# analog_channel.net
KiCad netlist of a schematic drawn in Altium Designer
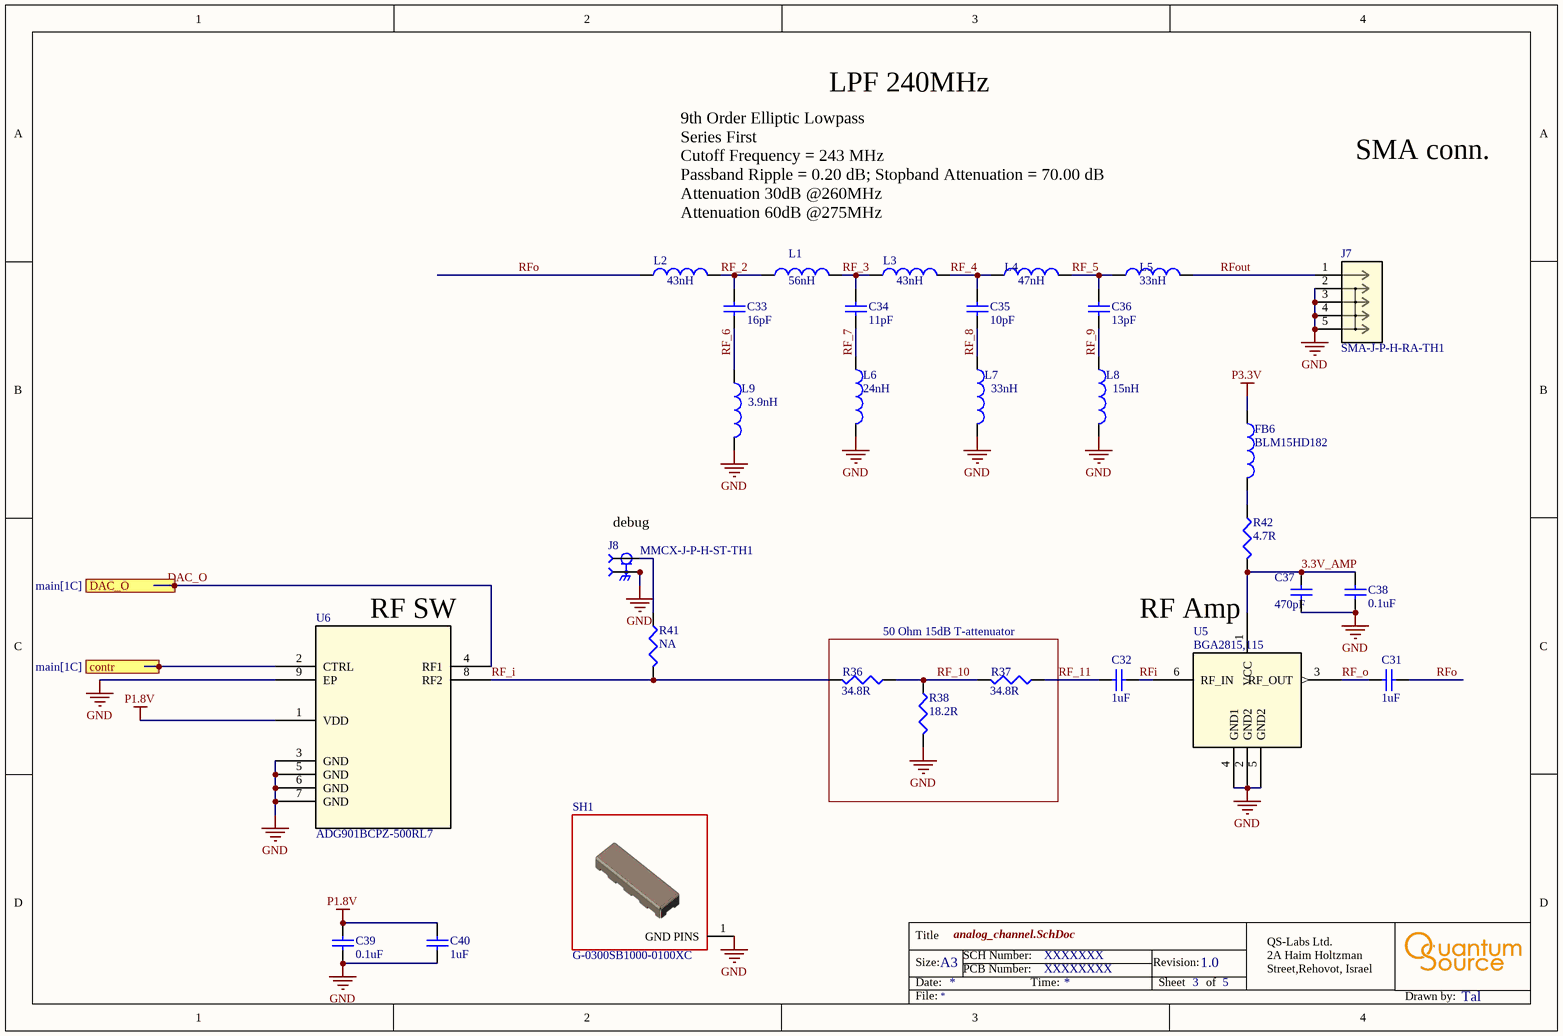
[diagram p0: analog_channel.SchDoc]

(export (version "E")
  (design (tool "Eeschema 10.0.6"))
  (components
    (comp (ref "C31")
      (value "1uF 25V")
      (footprint "C0402")
      (description "CAP CER 1uF 25V X5R 0402")
      (fields
        (field (name "MANUFACTURER PART NUMBER") "C1005C0G1H6R8D")
        (field (name "MANUFACTURER") "TDK Corporation")
        (field (name "CAPACITANCE") "1uF")
      )
      (libsource (lib "L_SCH_C") (part "CAP CER 6.8pF 50V NP0 0402"))
    )
    (comp (ref "C32")
      (value "1uF 25V")
      (footprint "C0402")
      (description "CAP CER 1uF 25V X5R 0402")
      (fields
        (field (name "MANUFACTURER PART NUMBER") "C1005C0G1H6R8D")
        (field (name "MANUFACTURER") "TDK Corporation")
        (field (name "CAPACITANCE") "1uF")
      )
      (libsource (lib "L_SCH_C") (part "CAP CER 6.8pF 50V NP0 0402"))
    )
    (comp (ref "C33")
      (value "16pF 50V")
      (footprint "C0402")
      (description "CAP CER 16PF 50V 5% NP0 0402")
      (fields
        (field (name "MANUFACTURER") "TDK Corporation")
        (field (name "MANUFACTURER PART NUMBER") "C1005C0G1H200J")
        (field (name "CAPACITANCE") "16pF")
      )
      (libsource (lib "L_SCH_C") (part "CAP CER 20pF 50V 5% NP0 0402"))
    )
    (comp (ref "C34")
      (value "11pF 50V")
      (footprint "C0402")
      (description "CAP CER 11PF 50V 5% NP0 0402")
      (fields
        (field (name "MANUFACTURER") "TDK Corporation")
        (field (name "MANUFACTURER PART NUMBER") "C1005C0G1H200J")
        (field (name "CAPACITANCE") "11pF")
      )
      (libsource (lib "L_SCH_C") (part "CAP CER 20pF 50V 5% NP0 0402"))
    )
    (comp (ref "C35")
      (value "10pF 50V")
      (footprint "C0402")
      (description "CAP CER 10PF 50V 5% NP0 0402")
      (fields
        (field (name "MANUFACTURER") "TDK Corporation")
        (field (name "MANUFACTURER PART NUMBER") "C1005C0G1H200J")
        (field (name "CAPACITANCE") "10pF")
      )
      (libsource (lib "L_SCH_C") (part "CAP CER 20pF 50V 5% NP0 0402"))
    )
    (comp (ref "C36")
      (value "13pF 50V")
      (footprint "C0402")
      (description "CAP CER 13PF 50V 5% NP0 0402")
      (fields
        (field (name "MANUFACTURER") "TDK Corporation")
        (field (name "MANUFACTURER PART NUMBER") "C1005C0G1H200J")
        (field (name "CAPACITANCE") "13pF")
      )
      (libsource (lib "L_SCH_C") (part "CAP CER 20pF 50V 5% NP0 0402"))
    )
    (comp (ref "C37")
      (value "470pF 25V")
      (footprint "C0402")
      (description "CAP CER 470pF 25V X5R 0402")
      (fields
        (field (name "MANUFACTURER PART NUMBER") "C1005C0G1H6R8D")
        (field (name "MANUFACTURER") "TDK Corporation")
        (field (name "CAPACITANCE") "470pF")
      )
      (libsource (lib "L_SCH_C") (part "CAP CER 6.8pF 50V NP0 0402"))
    )
    (comp (ref "C38")
      (value "0.1uF 50V")
      (footprint "C0402")
      (description "CAP CER 0.1uF 50V NP0 0402")
      (fields
        (field (name "MANUFACTURER PART NUMBER") "C1005C0G1H6R8D")
        (field (name "MANUFACTURER") "TDK Corporation")
        (field (name "CAPACITANCE") "0.1uF")
      )
      (libsource (lib "L_SCH_C") (part "CAP CER 6.8pF 50V NP0 0402"))
    )
    (comp (ref "C39")
      (value "0.1uF 50V")
      (footprint "C0402")
      (description "CAP CER 0.1uF 50V NP0 0402")
      (fields
        (field (name "MANUFACTURER PART NUMBER") "C1005C0G1H6R8D")
        (field (name "MANUFACTURER") "TDK Corporation")
        (field (name "CAPACITANCE") "0.1uF")
      )
      (libsource (lib "L_SCH_C") (part "CAP CER 6.8pF 50V NP0 0402"))
    )
    (comp (ref "C40")
      (value "1uF 25V")
      (footprint "C0402")
      (description "CAP CER 1uF 25V X5R 0402")
      (fields
        (field (name "MANUFACTURER PART NUMBER") "C1005C0G1H6R8D")
        (field (name "MANUFACTURER") "TDK Corporation")
        (field (name "CAPACITANCE") "1uF")
      )
      (libsource (lib "L_SCH_C") (part "CAP CER 6.8pF 50V NP0 0402"))
    )
    (comp (ref "FB6")
      (value "BLM15HD182")
      (footprint "0402-A")
      (description "FERRITE BEAD 1.8K OHM 0402 1LN")
      (fields
        (field (name "MANUFACTURER") "Taiyo Yuden")
        (field (name "MANUFACTURER PART NUMBER") "BLM15HD182")
      )
      (libsource (lib "DDS_PCB_1") (part "BK1608HS600-T"))
    )
    (comp (ref "J7")
      (value "SMA-J-P-H-RA-TH1")
      (footprint "CONN_SMA-J-P-H-RA-TH1_SAI")
      (description "No Description Available")
      (fields (field (name "COPYRIGHT") "Copyright (C) 2023 Ultra Librarian. All rights reserved."))
      (libsource (lib "SMA-J-P-H-RA-TH1") (part "SMA-J-P-H-RA-TH1"))
    )
    (comp (ref "J8")
      (value "MMCX-J-P-H-ST-TH1")
      (footprint "SAMTEC_MMCX-J-P-H-ST-TH1")
      (description "MMCX STRAIGHT, THROUGH HOLE JACK- 50 OHM")
      (fields (field (name "MF") "Samtec"))
      (libsource (lib "MMCX-J-P-H-ST-TH1") (part "MMCX-J-P-H-ST-TH1"))
    )
    (comp (ref "L1")
      (value "56nH")
      (footprint "0402-A")
      (description "Inductor")
      (fields (field (name "PUBLISHER") "Altium Limited"))
      (libsource (lib "Miscellaneous Devices") (part "Inductor"))
    )
    (comp (ref "L2")
      (value "43nH")
      (footprint "0402-A")
      (description "Inductor")
      (fields (field (name "PUBLISHER") "Altium Limited"))
      (libsource (lib "Miscellaneous Devices") (part "Inductor"))
    )
    (comp (ref "L3")
      (value "43nH")
      (footprint "0402-A")
      (description "Inductor")
      (fields (field (name "PUBLISHER") "Altium Limited"))
      (libsource (lib "Miscellaneous Devices") (part "Inductor"))
    )
    (comp (ref "L4")
      (value "47nH")
      (footprint "0402-A")
      (description "Inductor")
      (fields (field (name "PUBLISHER") "Altium Limited"))
      (libsource (lib "Miscellaneous Devices") (part "Inductor"))
    )
    (comp (ref "L5")
      (value "33nH")
      (footprint "0402-A")
      (description "Inductor")
      (fields (field (name "PUBLISHER") "Altium Limited"))
      (libsource (lib "Miscellaneous Devices") (part "Inductor"))
    )
    (comp (ref "L6")
      (value "24nH")
      (footprint "0402-A")
      (description "Inductor")
      (fields (field (name "PUBLISHER") "Altium Limited"))
      (libsource (lib "Miscellaneous Devices") (part "Inductor"))
    )
    (comp (ref "L7")
      (value "33nH")
      (footprint "0402-A")
      (description "Inductor")
      (fields (field (name "PUBLISHER") "Altium Limited"))
      (libsource (lib "Miscellaneous Devices") (part "Inductor"))
    )
    (comp (ref "L8")
      (value "15nH")
      (footprint "0402-A")
      (description "Inductor")
      (fields (field (name "PUBLISHER") "Altium Limited"))
      (libsource (lib "Miscellaneous Devices") (part "Inductor"))
    )
    (comp (ref "L9")
      (value "3.9nH")
      (footprint "0402-A")
      (description "Inductor")
      (fields (field (name "PUBLISHER") "Altium Limited"))
      (libsource (lib "Miscellaneous Devices") (part "Inductor"))
    )
    (comp (ref "R36")
      (value "34.8R")
      (footprint "r0402")
      (description "RES 34.8 OHM 1/10W 1% 0402 SMD")
      (fields
        (field (name "MANUFACTURER PART NUMBER") "ERJ-2RKF1000X")
        (field (name "MANUFACTURER") "Panasonic Electronic Components")
      )
      (libsource (lib "L_SCH_R") (part "RES 100 OHM 1/10W 1% 0402 SMD"))
    )
    (comp (ref "R37")
      (value "34.8R")
      (footprint "r0402")
      (description "RES 34.8 OHM 1/10W 1% 0402 SMD")
      (fields
        (field (name "MANUFACTURER PART NUMBER") "ERJ-2RKF1000X")
        (field (name "MANUFACTURER") "Panasonic Electronic Components")
      )
      (libsource (lib "L_SCH_R") (part "RES 100 OHM 1/10W 1% 0402 SMD"))
    )
    (comp (ref "R38")
      (value "18.2R")
      (footprint "r0402")
      (description "RES 18.2 OHM 1/10W 1% 0402 SMD")
      (fields
        (field (name "MANUFACTURER PART NUMBER") "ERJ-2RKF1000X")
        (field (name "MANUFACTURER") "Panasonic Electronic Components")
      )
      (libsource (lib "L_SCH_R") (part "RES 100 OHM 1/10W 1% 0402 SMD"))
    )
    (comp (ref "R41")
      (value "NA")
      (footprint "r0402")
      (description "RES 0 OHM 1/10W 1% 0402 SMD")
      (fields
        (field (name "MANUFACTURER PART NUMBER") "ERJ-2RKF1000X")
        (field (name "MANUFACTURER") "Panasonic Electronic Components")
      )
      (libsource (lib "L_SCH_R") (part "RES 100 OHM 1/10W 1% 0402 SMD"))
    )
    (comp (ref "R42")
      (value "4.7R")
      (footprint "r0402")
      (description "RES 18.2 OHM 1/10W 1% 0402 SMD")
      (fields
        (field (name "MANUFACTURER PART NUMBER") "ERJ-2RKF1000X")
        (field (name "MANUFACTURER") "Panasonic Electronic Components")
      )
      (libsource (lib "L_SCH_R") (part "RES 100 OHM 1/10W 1% 0402 SMD"))
    )
    (comp (ref "SH1")
      (value "G-0300SB1000-0100XC")
      (footprint "RF_Sh")
      (description "RF Shield Cover 0.300\" (7.62mm) X 1.000\" (25.40mm) Non-Vented Surface Mount")
      (fields (field (name "MANUFACTURER") "Orbel Corporation"))
      (libsource (lib "DDS_PCB_1") (part "RF_SHIELD_1"))
    )
    (comp (ref "U5")
      (value "BGA2815,115")
      (footprint "SOT_2815,115_NXP")
      (description "No Description Available")
      (fields (field (name "COPYRIGHT") "Copyright (C) 2023 Ultra Librarian. All rights reserved."))
      (libsource (lib "BGA2815,115") (part "BGA2815,115"))
    )
    (comp (ref "U6")
      (value "ADG901BCPZ-500RL7")
      (footprint "CP_8_2_ADI")
      (description "No Description Available")
      (fields (field (name "COPYRIGHT") "Copyright (C) 2023 Ultra Librarian. All rights reserved."))
      (libsource (lib "ADG901BCPZ-500RL7") (part "ADG901BCPZ-500RL7"))
    )
  )
  (nets
    (net (code "1") (name "/3.3V_AMP") (class "Default")
      (node (ref "C37") (pin "2") (pinfunction "2_2") (pintype "passive"))
      (node (ref "C38") (pin "2") (pinfunction "2_2") (pintype "passive"))
      (node (ref "R42") (pin "2") (pinfunction "2_2") (pintype "passive"))
      (node (ref "U5") (pin "1") (pinfunction "VCC_1") (pintype "power_in"))
    )
    (net (code "2") (name "/DAC_O") (class "Default")
      (node (ref "U6") (pin "4") (pinfunction "RF1_4") (pintype "passive"))
    )
    (net (code "3") (name "/RF_2") (class "Default")
      (node (ref "C33") (pin "1") (pinfunction "1_1") (pintype "passive"))
      (node (ref "L1") (pin "1") (pinfunction "1_1") (pintype "passive"))
      (node (ref "L2") (pin "2") (pinfunction "2_2") (pintype "passive"))
    )
    (net (code "4") (name "/RF_3") (class "Default")
      (node (ref "C34") (pin "1") (pinfunction "1_1") (pintype "passive"))
      (node (ref "L1") (pin "2") (pinfunction "2_2") (pintype "passive"))
      (node (ref "L3") (pin "1") (pinfunction "1_1") (pintype "passive"))
    )
    (net (code "5") (name "/RF_4") (class "Default")
      (node (ref "C35") (pin "1") (pinfunction "1_1") (pintype "passive"))
      (node (ref "L3") (pin "2") (pinfunction "2_2") (pintype "passive"))
      (node (ref "L4") (pin "1") (pinfunction "1_1") (pintype "passive"))
    )
    (net (code "6") (name "/RF_5") (class "Default")
      (node (ref "C36") (pin "1") (pinfunction "1_1") (pintype "passive"))
      (node (ref "L4") (pin "2") (pinfunction "2_2") (pintype "passive"))
      (node (ref "L5") (pin "1") (pinfunction "1_1") (pintype "passive"))
    )
    (net (code "7") (name "/RF_6") (class "Default")
      (node (ref "C33") (pin "2") (pinfunction "2_2") (pintype "passive"))
      (node (ref "L9") (pin "1") (pinfunction "1_1") (pintype "passive"))
    )
    (net (code "8") (name "/RF_7") (class "Default")
      (node (ref "C34") (pin "2") (pinfunction "2_2") (pintype "passive"))
      (node (ref "L6") (pin "1") (pinfunction "1_1") (pintype "passive"))
    )
    (net (code "9") (name "/RF_8") (class "Default")
      (node (ref "C35") (pin "2") (pinfunction "2_2") (pintype "passive"))
      (node (ref "L7") (pin "1") (pinfunction "1_1") (pintype "passive"))
    )
    (net (code "10") (name "/RF_9") (class "Default")
      (node (ref "C36") (pin "2") (pinfunction "2_2") (pintype "passive"))
      (node (ref "L8") (pin "1") (pinfunction "1_1") (pintype "passive"))
    )
    (net (code "11") (name "/RF_10") (class "Default")
      (node (ref "R36") (pin "1") (pinfunction "1_1") (pintype "passive"))
      (node (ref "R37") (pin "2") (pinfunction "2_2") (pintype "passive"))
      (node (ref "R38") (pin "1") (pinfunction "1_1") (pintype "passive"))
    )
    (net (code "12") (name "/RF_11") (class "Default")
      (node (ref "C32") (pin "1") (pinfunction "1_1") (pintype "passive"))
      (node (ref "R37") (pin "1") (pinfunction "1_1") (pintype "passive"))
    )
    (net (code "13") (name "/RF_i") (class "Default")
      (node (ref "R36") (pin "2") (pinfunction "2_2") (pintype "passive"))
      (node (ref "R41") (pin "2") (pinfunction "2_2") (pintype "passive"))
      (node (ref "U6") (pin "8") (pinfunction "RF2_8") (pintype "passive"))
    )
    (net (code "14") (name "/RF_o") (class "Default")
      (node (ref "C31") (pin "1") (pinfunction "1_1") (pintype "passive"))
      (node (ref "U5") (pin "3") (pinfunction "RF_OUT_3") (pintype "output"))
    )
    (net (code "15") (name "/RFi") (class "Default")
      (node (ref "C32") (pin "2") (pinfunction "2_2") (pintype "passive"))
      (node (ref "U5") (pin "6") (pinfunction "RF_IN_6") (pintype "passive"))
    )
    (net (code "16") (name "/RFo") (class "Default")
      (node (ref "C31") (pin "2") (pinfunction "2_2") (pintype "passive"))
      (node (ref "L2") (pin "1") (pinfunction "1_1") (pintype "passive"))
    )
    (net (code "17") (name "/RFout") (class "Default")
      (node (ref "J7") (pin "1") (pinfunction "1_1") (pintype "passive"))
      (node (ref "L5") (pin "2") (pinfunction "2_2") (pintype "passive"))
    )
    (net (code "18") (name "/contr") (class "Default")
      (node (ref "U6") (pin "2") (pinfunction "CTRL_2") (pintype "passive"))
    )
    (net (code "19") (name "GND") (class "Default")
      (node (ref "C37") (pin "1") (pinfunction "1_1") (pintype "passive"))
      (node (ref "C38") (pin "1") (pinfunction "1_1") (pintype "passive"))
      (node (ref "C39") (pin "1") (pinfunction "1_1") (pintype "passive"))
      (node (ref "C40") (pin "1") (pinfunction "1_1") (pintype "passive"))
      (node (ref "J7") (pin "2") (pinfunction "2_2") (pintype "passive"))
      (node (ref "J7") (pin "3") (pinfunction "3_3") (pintype "passive"))
      (node (ref "J7") (pin "4") (pinfunction "4_4") (pintype "passive"))
      (node (ref "J7") (pin "5") (pinfunction "5_5") (pintype "passive"))
      (node (ref "J8") (pin "S1") (pinfunction "2_S1") (pintype "passive"))
      (node (ref "J8") (pin "S2") (pinfunction "2_S2") (pintype "passive"))
      (node (ref "J8") (pin "S3") (pinfunction "2_S3") (pintype "passive"))
      (node (ref "J8") (pin "S4") (pinfunction "2_S4") (pintype "passive"))
      (node (ref "L6") (pin "2") (pinfunction "2_2") (pintype "passive"))
      (node (ref "L7") (pin "2") (pinfunction "2_2") (pintype "passive"))
      (node (ref "L8") (pin "2") (pinfunction "2_2") (pintype "passive"))
      (node (ref "L9") (pin "2") (pinfunction "2_2") (pintype "passive"))
      (node (ref "R38") (pin "2") (pinfunction "2_2") (pintype "passive"))
      (node (ref "SH1") (pin "1") (pinfunction "GND_PINS_1") (pintype "passive"))
      (node (ref "U5") (pin "2") (pinfunction "GND2_2") (pintype "passive"))
      (node (ref "U5") (pin "4") (pinfunction "GND1_4") (pintype "passive"))
      (node (ref "U5") (pin "5") (pinfunction "GND2_5") (pintype "passive"))
      (node (ref "U6") (pin "3") (pinfunction "GND_3") (pintype "passive"))
      (node (ref "U6") (pin "5") (pinfunction "GND_5") (pintype "passive"))
      (node (ref "U6") (pin "6") (pinfunction "GND_6") (pintype "passive"))
      (node (ref "U6") (pin "7") (pinfunction "GND_7") (pintype "passive"))
      (node (ref "U6") (pin "9") (pinfunction "EP_9") (pintype "passive"))
    )
    (net (code "20") (name "Net-(FB6-Pad2)") (class "Default")
      (node (ref "FB6") (pin "2") (pinfunction "2_2") (pintype "passive"))
      (node (ref "R42") (pin "1") (pinfunction "1_1") (pintype "passive"))
    )
    (net (code "21") (name "Net-(J8-Pad1)") (class "Default")
      (node (ref "J8") (pin "1") (pinfunction "1_1") (pintype "passive"))
      (node (ref "R41") (pin "1") (pinfunction "1_1") (pintype "passive"))
    )
    (net (code "22") (name "P1.8V") (class "Default")
      (node (ref "C39") (pin "2") (pinfunction "2_2") (pintype "passive"))
      (node (ref "C40") (pin "2") (pinfunction "2_2") (pintype "passive"))
      (node (ref "U6") (pin "1") (pinfunction "VDD_1") (pintype "power_in"))
    )
    (net (code "23") (name "P3.3V") (class "Default")
      (node (ref "FB6") (pin "1") (pinfunction "1_1") (pintype "passive"))
    )
  )
)
